# temperature.net
KiCad netlist of a schematic drawn in Altium Designer
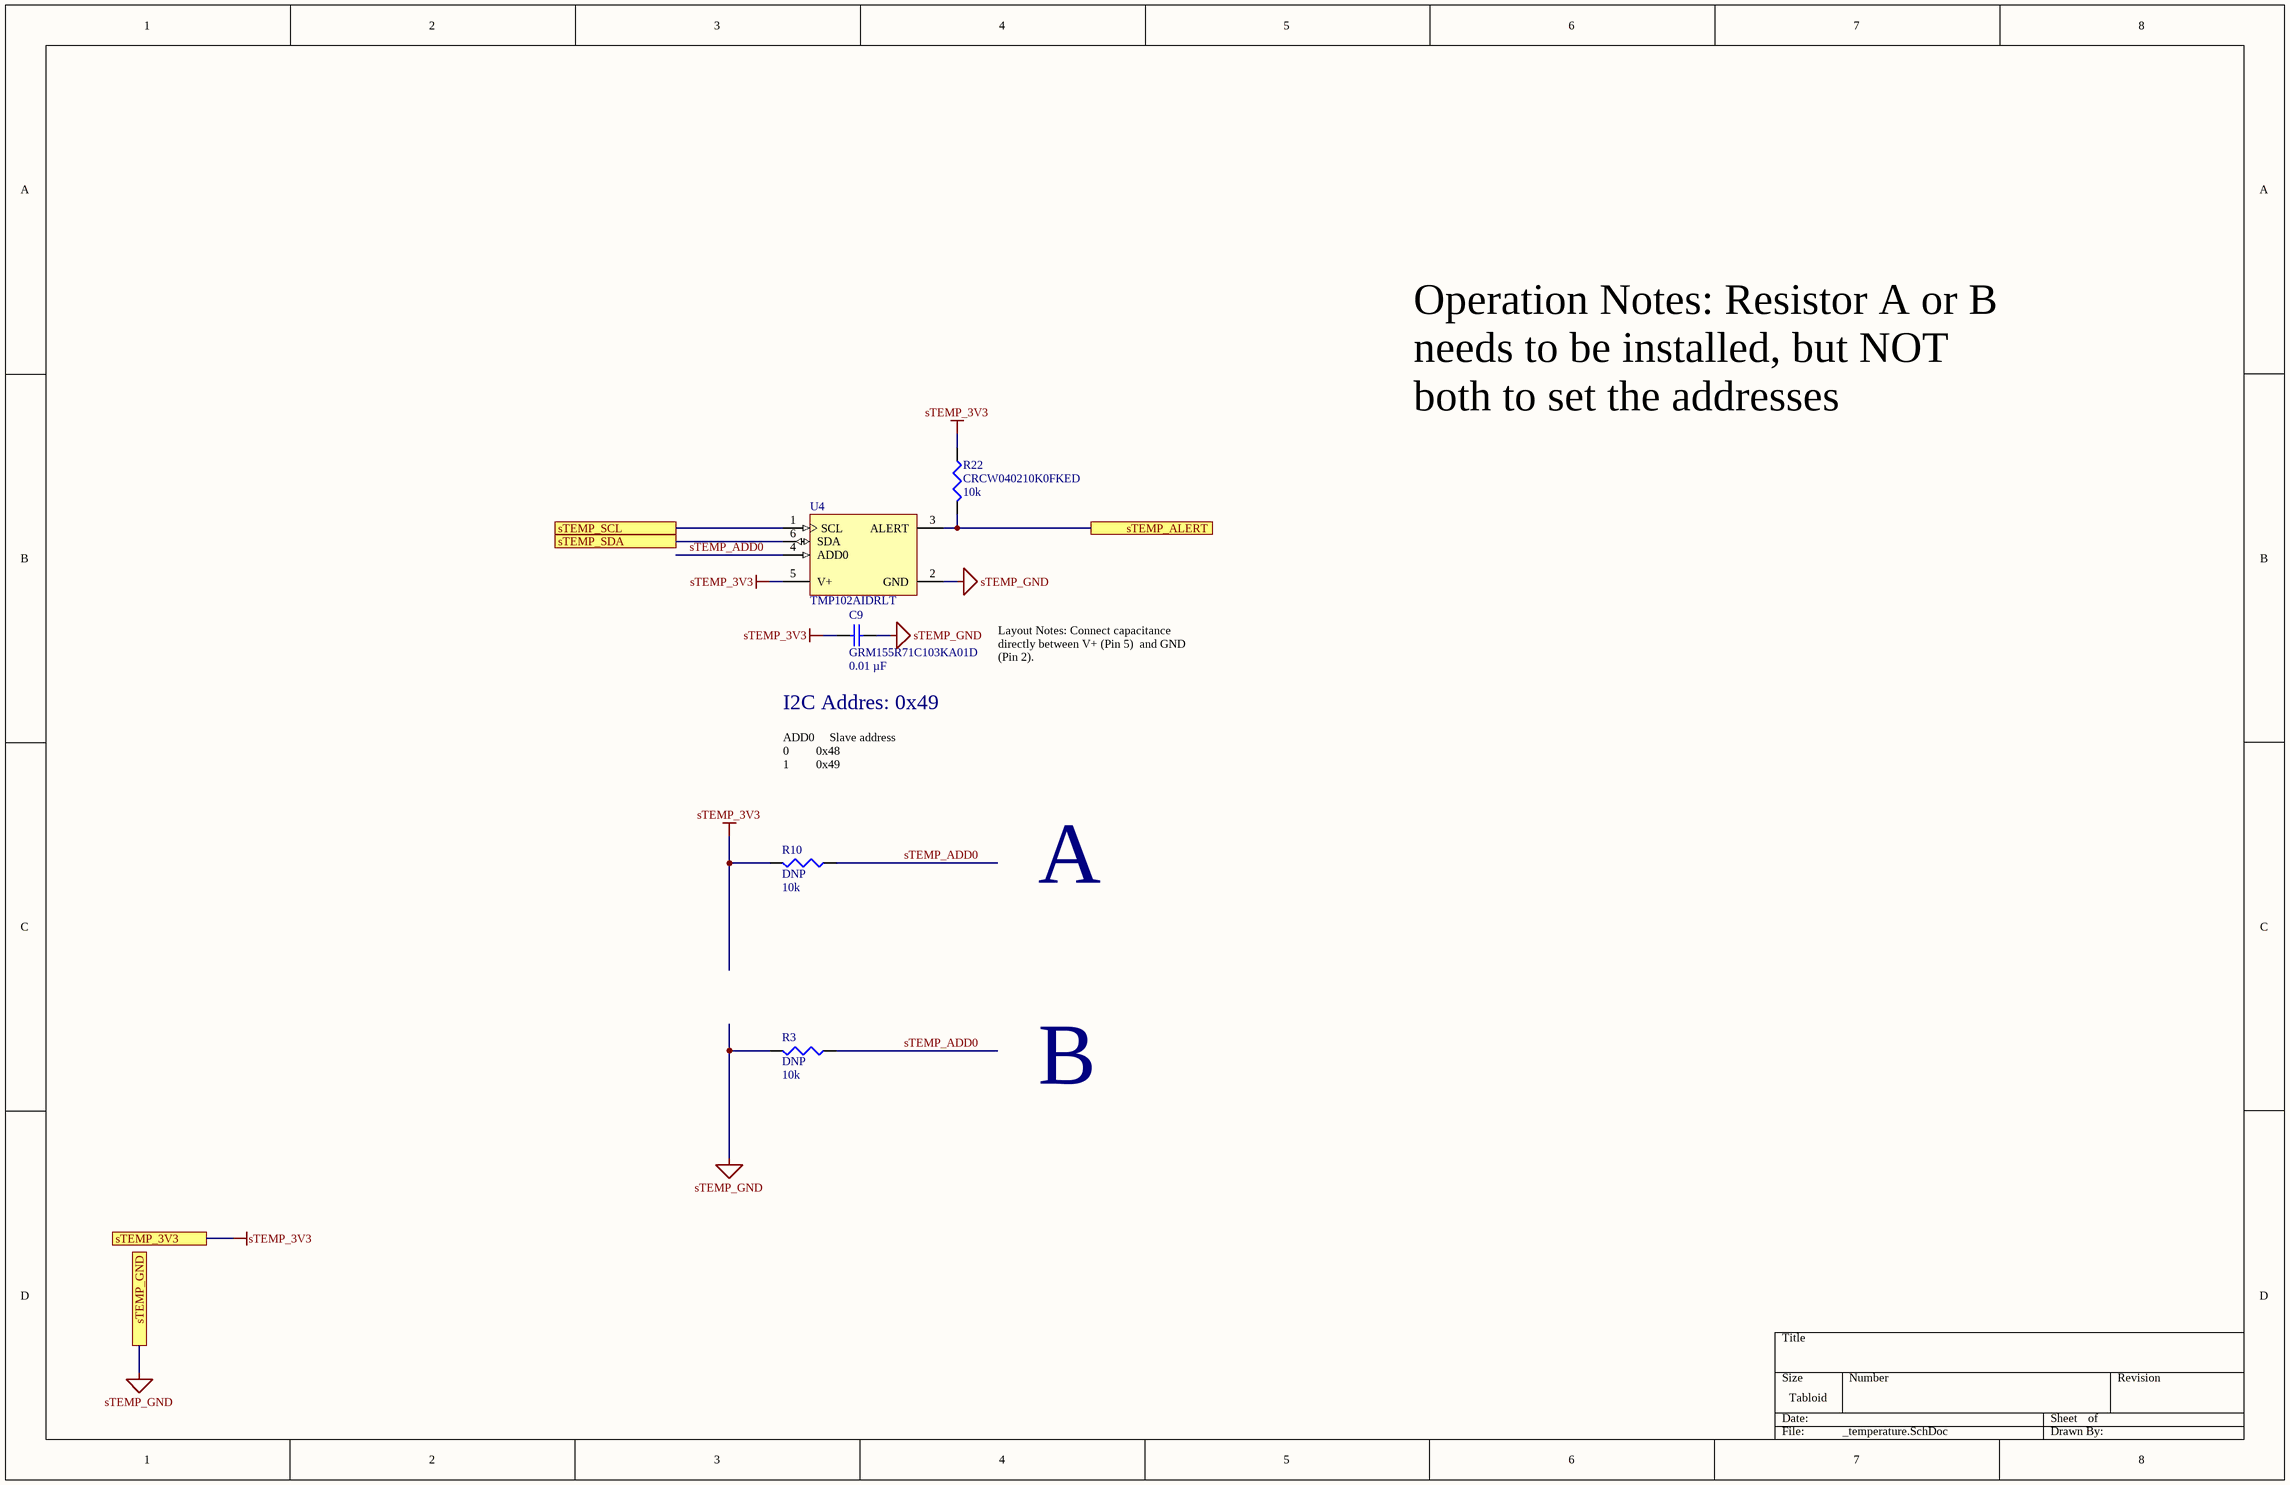
[diagram p0: _temperature.SchDoc]

(export (version "E")
  (design (tool "Eeschema 10.0.6"))
  (components
    (comp (ref "C9")
      (value "GRM155R71C103KA01D")
      (footprint "0402")
      (description "Cap, 0.01 µF, 16 V, X7R")
      (fields (field (name "ALTIUM_VALUE") "0.01 µF") (field (name "PUBLISHER") "Altium Limited"))
      (libsource (lib "miscellaneous_devices") (part "Cap"))
    )
    (comp (ref "R3")
      (value "DNP")
      (footprint "0402")
      (description "0.125W, -55-155C, 1005, 50V, ±1%")
      (fields (field (name "ALTIUM_VALUE") "10k"))
      (libsource (lib "standard_resistors") (part "CRCW0402xxxxFKED"))
    )
    (comp (ref "R10")
      (value "DNP")
      (footprint "0402")
      (description "0.125W, -55-155C, 1005, 50V, ±1%")
      (fields (field (name "ALTIUM_VALUE") "10k"))
      (libsource (lib "standard_resistors") (part "CRCW0402xxxxFKED"))
    )
    (comp (ref "R22")
      (value "CRCW040210K0FKED")
      (footprint "0402")
      (description "0.125W, -55-155C, 1005, 50V, ±1%")
      (fields (field (name "ALTIUM_VALUE") "10k"))
      (libsource (lib "standard_resistors") (part "CRCW0402xxxxFKED"))
    )
    (comp (ref "U4")
      (value "TMP102AIDRLT")
      (footprint "DRL0006A_L")
      (libsource (lib "Altium Content Vault") (part "TI-TMP102AIDRLT-DRL6"))
    )
  )
  (nets
    (net (code "1") (name "/sTEMP_ADD0") (class "Default")
      (node (ref "R10") (pin "1") (pinfunction "1_1") (pintype "passive"))
      (node (ref "R3") (pin "1") (pinfunction "1_1") (pintype "passive"))
      (node (ref "U4") (pin "4") (pinfunction "ADD0_4") (pintype "input"))
    )
    (net (code "2") (name "/sTEMP_ALERT") (class "Default")
      (node (ref "R22") (pin "2") (pinfunction "2_2") (pintype "passive"))
      (node (ref "U4") (pin "3") (pinfunction "ALERT_3") (pintype "open_collector"))
    )
    (net (code "3") (name "/sTEMP_SCL") (class "Default")
      (node (ref "U4") (pin "1") (pinfunction "SCL_1") (pintype "input"))
    )
    (net (code "4") (name "/sTEMP_SDA") (class "Default")
      (node (ref "U4") (pin "6") (pinfunction "SDA_6") (pintype "bidirectional"))
    )
    (net (code "5") (name "sTEMP_3V3") (class "Default")
      (node (ref "C9") (pin "2") (pinfunction "2_2") (pintype "passive"))
      (node (ref "R10") (pin "2") (pinfunction "2_2") (pintype "passive"))
      (node (ref "R22") (pin "1") (pinfunction "1_1") (pintype "passive"))
      (node (ref "U4") (pin "5") (pinfunction "V+_5") (pintype "power_in"))
    )
    (net (code "6") (name "sTEMP_GND") (class "Default")
      (node (ref "C9") (pin "1") (pinfunction "1_1") (pintype "passive"))
      (node (ref "R3") (pin "2") (pinfunction "2_2") (pintype "passive"))
      (node (ref "U4") (pin "2") (pinfunction "GND_2") (pintype "power_in"))
    )
  )
)
